# RTC.net
KiCad netlist of a schematic drawn in Altium Designer
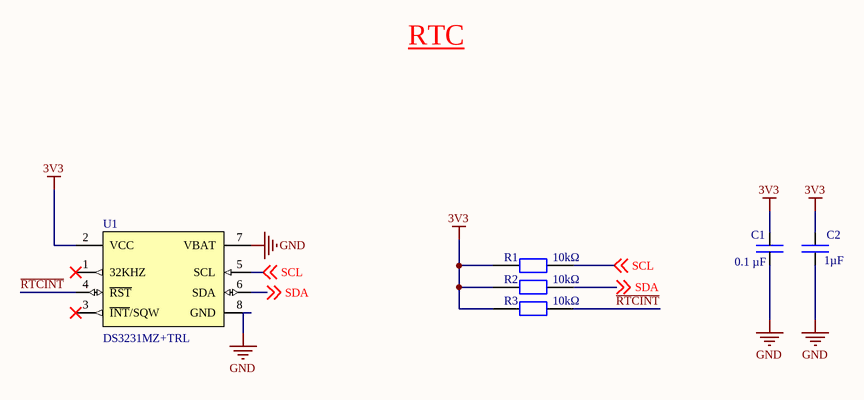
[diagram p0: RTC.SchDoc]

(export (version "E")
  (design (tool "Eeschema 10.0.6"))
  (components
    (comp (ref "C1")
      (value "0.1 µF")
      (description "Multilayer Ceramic Capacitors MLCC - SMD/SMT V 0.1uF X5R 0402 10%")
      (fields
        (field (name "MANUFACTURER") "Yageo Group")
        (field (name "MANUFACTURER PART NUMBER") "C0402C104K7PACTU")
      )
      (libsource (lib "Component_1") (part "C0402C104K7PACTU"))
    )
    (comp (ref "C2")
      (value "1µF")
      (description "Multilayer Ceramic Capacitors MLCC – SMD/SMT; KEMET; C0402C105K9PACTU; 1 µF; 0402; 6.3 V; 6.3 V")
      (fields
        (field (name "MANUFACTURER") "Yageo Group")
        (field (name "MANUFACTURER PART NUMBER") "C0402C105K9PACTU")
      )
      (libsource (lib "Component_1") (part "C0402C105K9PACTU"))
    )
    (comp (ref "R1")
      (value "10kΩ")
      (description "125mW Thin Film Resistor 150V ±25ppm/℃ ±0.1% 10kΩ 0805 Chip Resistor - Surface Mount ROHS")
      (fields
        (field (name "MANUFACTURER") "Yageo Group")
        (field (name "MANUFACTURER PART NUMBER") "RT0805BRD0710KL")
      )
      (libsource (lib "Component_1") (part "RT0805BRD0710KL"))
    )
    (comp (ref "R2")
      (value "10kΩ")
      (description "125mW Thin Film Resistor 150V ±25ppm/℃ ±0.1% 10kΩ 0805 Chip Resistor - Surface Mount ROHS")
      (fields
        (field (name "MANUFACTURER") "Yageo Group")
        (field (name "MANUFACTURER PART NUMBER") "RT0805BRD0710KL")
      )
      (libsource (lib "Component_1") (part "RT0805BRD0710KL"))
    )
    (comp (ref "R3")
      (value "10kΩ")
      (description "125mW Thin Film Resistor 150V ±25ppm/℃ ±0.1% 10kΩ 0805 Chip Resistor - Surface Mount ROHS")
      (fields
        (field (name "MANUFACTURER") "Yageo Group")
        (field (name "MANUFACTURER PART NUMBER") "RT0805BRD0710KL")
      )
      (libsource (lib "Component_1") (part "RT0805BRD0710KL"))
    )
    (comp (ref "U1")
      (value "DS3231MZ+TRL")
      (footprint "DS3231MZ+TRL")
      (description "HH: MM: SS (12/24 hr) 128bit 2.3V 5.5V 2, I2C, Serial YY-MM-DD-dd SOIC-8 4.9mm*3.9mm*1.55mm")
      (fields (field (name "MANUFACTURER") "Analog Devices"))
      (libsource (lib "Component_1") (part "DS3231MZ+TRL"))
    )
  )
  (nets
    (net (code "1") (name "/~{RTCINT}") (class "Default")
      (node (ref "R3") (pin "2") (pinfunction "2_2") (pintype "passive"))
      (node (ref "U1") (pin "4") (pinfunction "~{RST}_4") (pintype "bidirectional"))
    )
    (net (code "2") (name "3V3") (class "Default")
      (node (ref "C1") (pin "2") (pinfunction "2_2") (pintype "passive"))
      (node (ref "C2") (pin "1") (pinfunction "12_1") (pintype "passive"))
      (node (ref "R1") (pin "1") (pinfunction "1_1") (pintype "passive"))
      (node (ref "R2") (pin "1") (pinfunction "1_1") (pintype "passive"))
      (node (ref "R3") (pin "1") (pinfunction "1_1") (pintype "passive"))
      (node (ref "U1") (pin "2") (pinfunction "VCC_2") (pintype "power_in"))
    )
    (net (code "3") (name "GND") (class "Default")
      (node (ref "C1") (pin "1") (pinfunction "1_1") (pintype "passive"))
      (node (ref "C2") (pin "2") (pinfunction "12_2") (pintype "passive"))
      (node (ref "U1") (pin "7") (pinfunction "VBAT_7") (pintype "power_in"))
      (node (ref "U1") (pin "8") (pinfunction "GND_8") (pintype "power_in"))
    )
    (net (code "4") (name "SCL") (class "Default")
      (node (ref "R1") (pin "2") (pinfunction "2_2") (pintype "passive"))
      (node (ref "U1") (pin "5") (pinfunction "SCL_5") (pintype "input"))
    )
    (net (code "5") (name "SDA") (class "Default")
      (node (ref "R2") (pin "2") (pinfunction "2_2") (pintype "passive"))
      (node (ref "U1") (pin "6") (pinfunction "SDA_6") (pintype "bidirectional"))
    )
    (net (code "6") (name "unconnected-(U1-32KHZ-Pad1)") (class "Default")
      (node (ref "U1") (pin "1") (pinfunction "32KHZ_1") (pintype "output+no_connect"))
    )
    (net (code "7") (name "unconnected-(U1-~{INT}{slash}SQW-Pad3)") (class "Default")
      (node (ref "U1") (pin "3") (pinfunction "~{INT}/SQW_3") (pintype "output+no_connect"))
    )
  )
)
